# d_ff.net
KiCad netlist of a schematic drawn in EAGLE
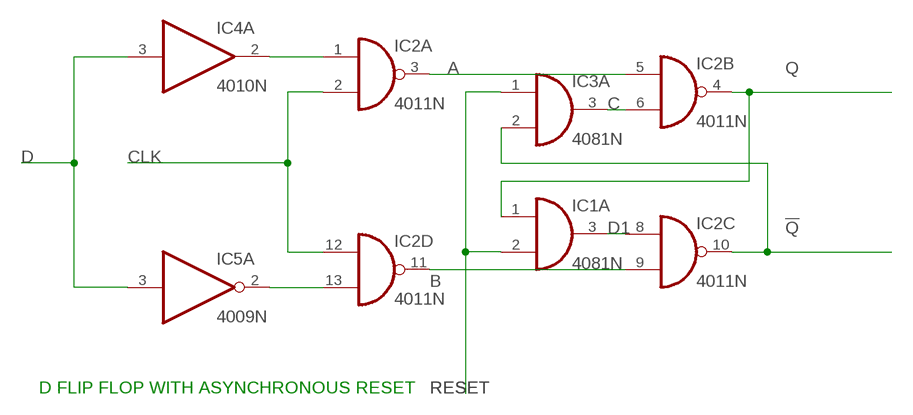
[diagram p0: schematic, sheet 1]

(export (version "E")
  (design (tool "Eeschema 10.0.6"))
  (components
    (comp (ref "IC1")
      (value "4081N")
      (footprint "eagle-import:DIL14")
      (libsource (lib "eagle-import") (part "4081N"))
    )
    (comp (ref "IC2")
      (value "4011N")
      (footprint "eagle-import:DIL14")
      (libsource (lib "eagle-import") (part "4011N"))
    )
    (comp (ref "IC3")
      (value "4081N")
      (footprint "eagle-import:DIL14")
      (libsource (lib "eagle-import") (part "4081N"))
    )
    (comp (ref "IC4")
      (value "4010N")
      (footprint "eagle-import:DIL16")
      (libsource (lib "eagle-import") (part "4010N"))
    )
    (comp (ref "IC5")
      (value "4009N")
      (footprint "eagle-import:DIL16")
      (libsource (lib "eagle-import") (part "4009N"))
    )
  )
  (nets
    (net (code "1") (name "/A") (class "Default")
      (node (ref "IC2") (pin "3") (pinfunction "O_3") (pintype "output"))
      (node (ref "IC2") (pin "5") (pinfunction "I0_5") (pintype "input"))
    )
    (net (code "2") (name "/B") (class "Default")
      (node (ref "IC2") (pin "11") (pinfunction "O_11") (pintype "output"))
      (node (ref "IC2") (pin "9") (pinfunction "I1_9") (pintype "input"))
    )
    (net (code "3") (name "/C") (class "Default")
      (node (ref "IC2") (pin "6") (pinfunction "I1_6") (pintype "input"))
      (node (ref "IC3") (pin "3") (pinfunction "O_3") (pintype "output"))
    )
    (net (code "4") (name "/CLK") (class "Default")
      (node (ref "IC2") (pin "12") (pinfunction "I0_12") (pintype "input"))
      (node (ref "IC2") (pin "2") (pinfunction "I1_2") (pintype "input"))
    )
    (net (code "5") (name "/D") (class "Default")
      (node (ref "IC4") (pin "3") (pinfunction "I_3") (pintype "input"))
      (node (ref "IC5") (pin "3") (pinfunction "I_3") (pintype "input"))
    )
    (net (code "6") (name "/D1") (class "Default")
      (node (ref "IC1") (pin "3") (pinfunction "O_3") (pintype "output"))
      (node (ref "IC2") (pin "8") (pinfunction "I0_8") (pintype "input"))
    )
    (net (code "7") (name "/Q") (class "Default")
      (node (ref "IC1") (pin "1") (pinfunction "I0_1") (pintype "input"))
      (node (ref "IC2") (pin "4") (pinfunction "O_4") (pintype "output"))
    )
    (net (code "8") (name "/RESET") (class "Default")
      (node (ref "IC1") (pin "2") (pinfunction "I1_2") (pintype "input"))
      (node (ref "IC3") (pin "1") (pinfunction "I0_1") (pintype "input"))
    )
    (net (code "9") (name "/~{Q}") (class "Default")
      (node (ref "IC2") (pin "10") (pinfunction "O_10") (pintype "output"))
      (node (ref "IC3") (pin "2") (pinfunction "I1_2") (pintype "input"))
    )
    (net (code "10") (name "Net-(IC2A-I0)") (class "Default")
      (node (ref "IC2") (pin "1") (pinfunction "I0_1") (pintype "input"))
      (node (ref "IC4") (pin "2") (pinfunction "O_2") (pintype "output"))
    )
    (net (code "11") (name "Net-(IC2D-I1)") (class "Default")
      (node (ref "IC2") (pin "13") (pinfunction "I1_13") (pintype "input"))
      (node (ref "IC5") (pin "2") (pinfunction "O_2") (pintype "output"))
    )
  )
)
